# SparkFun_Thing_Plus_RA6M5.net
KiCad netlist of a schematic drawn in EAGLE
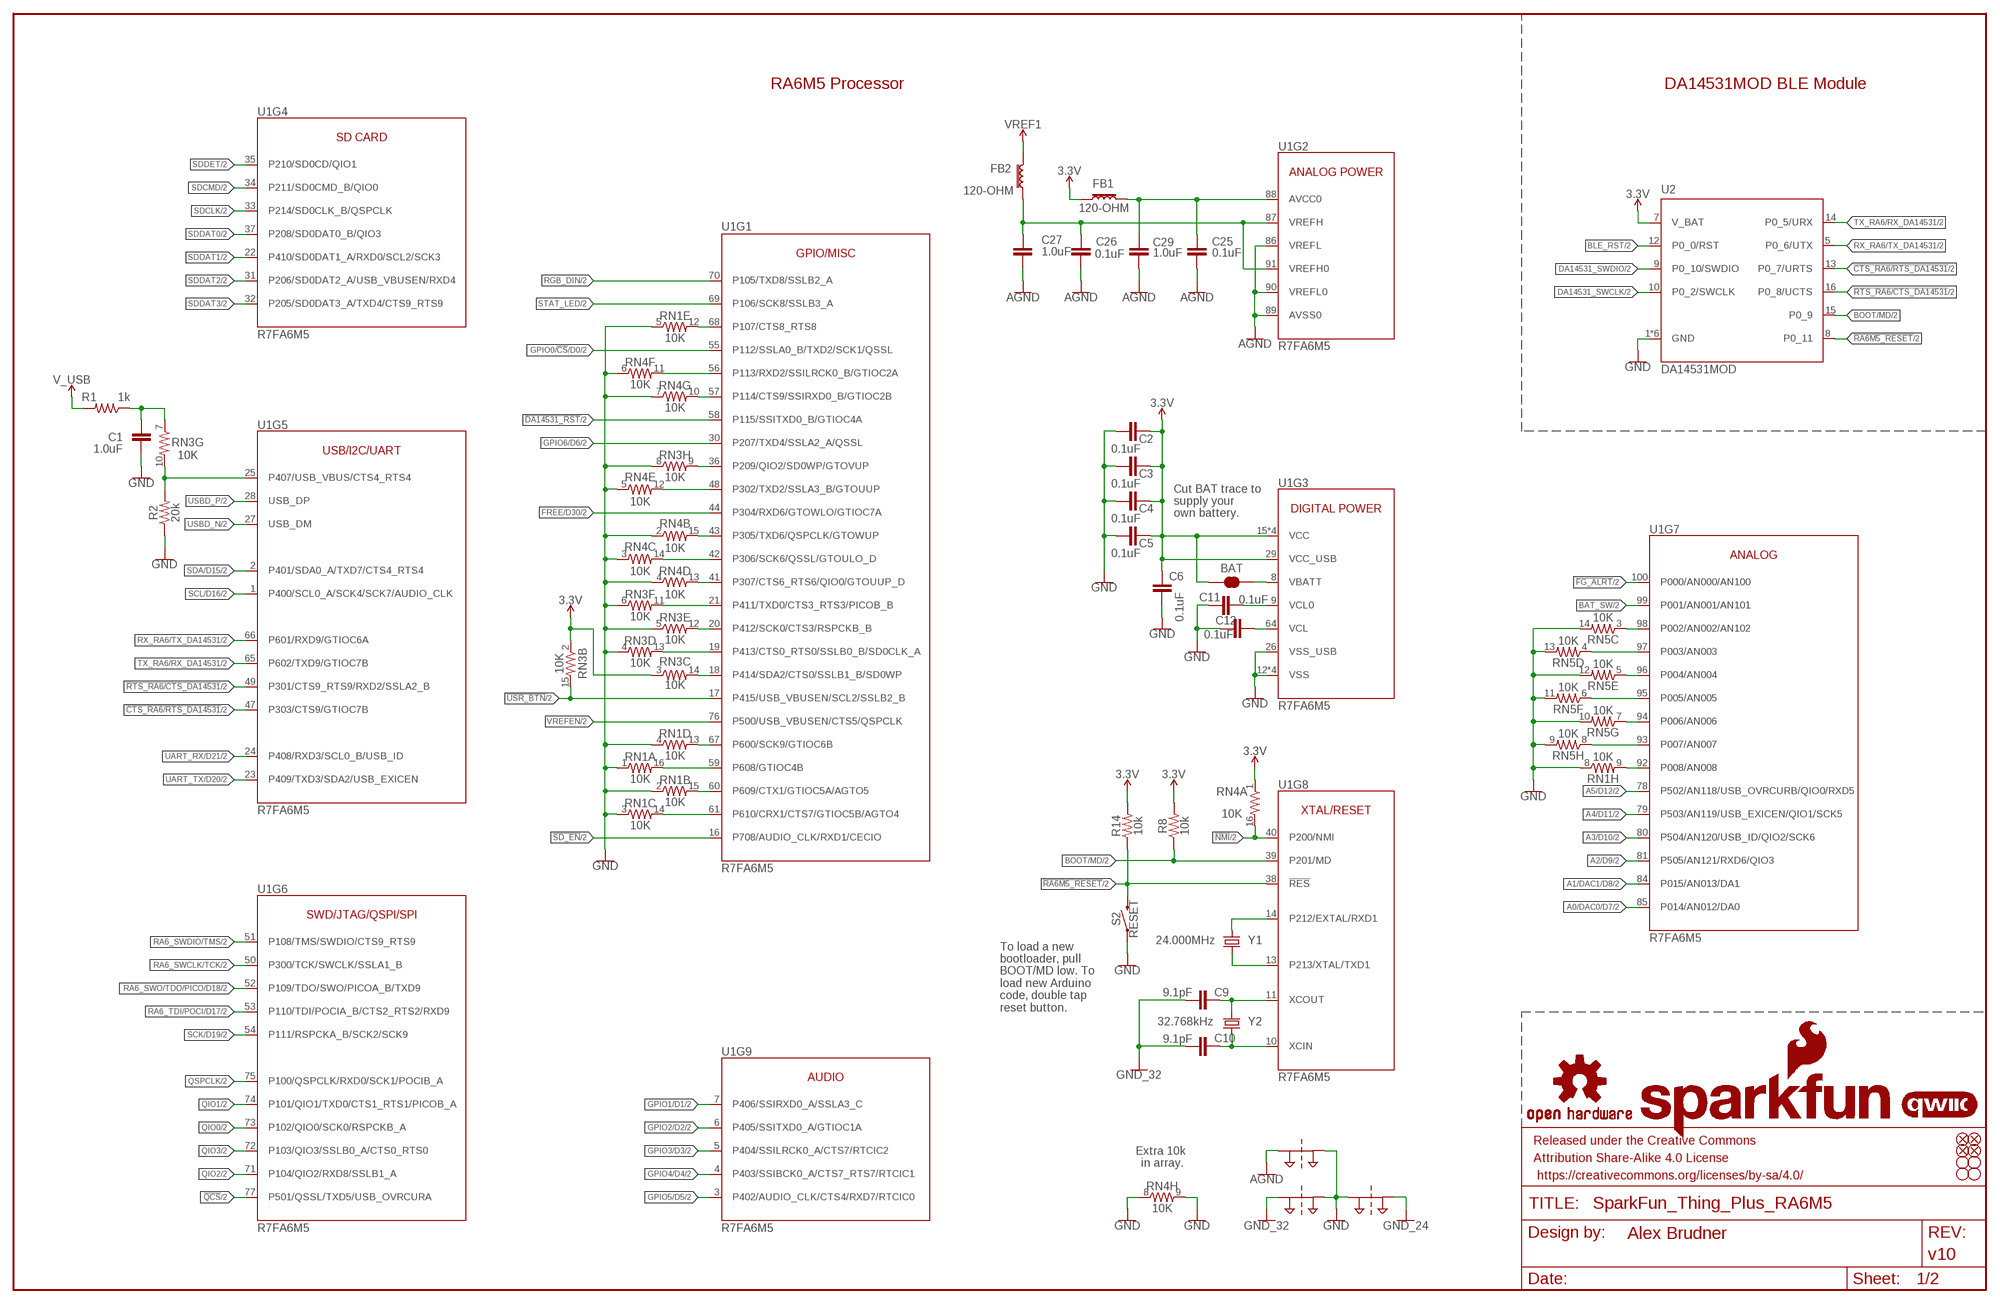
[diagram p0: schematic, sheet 1]
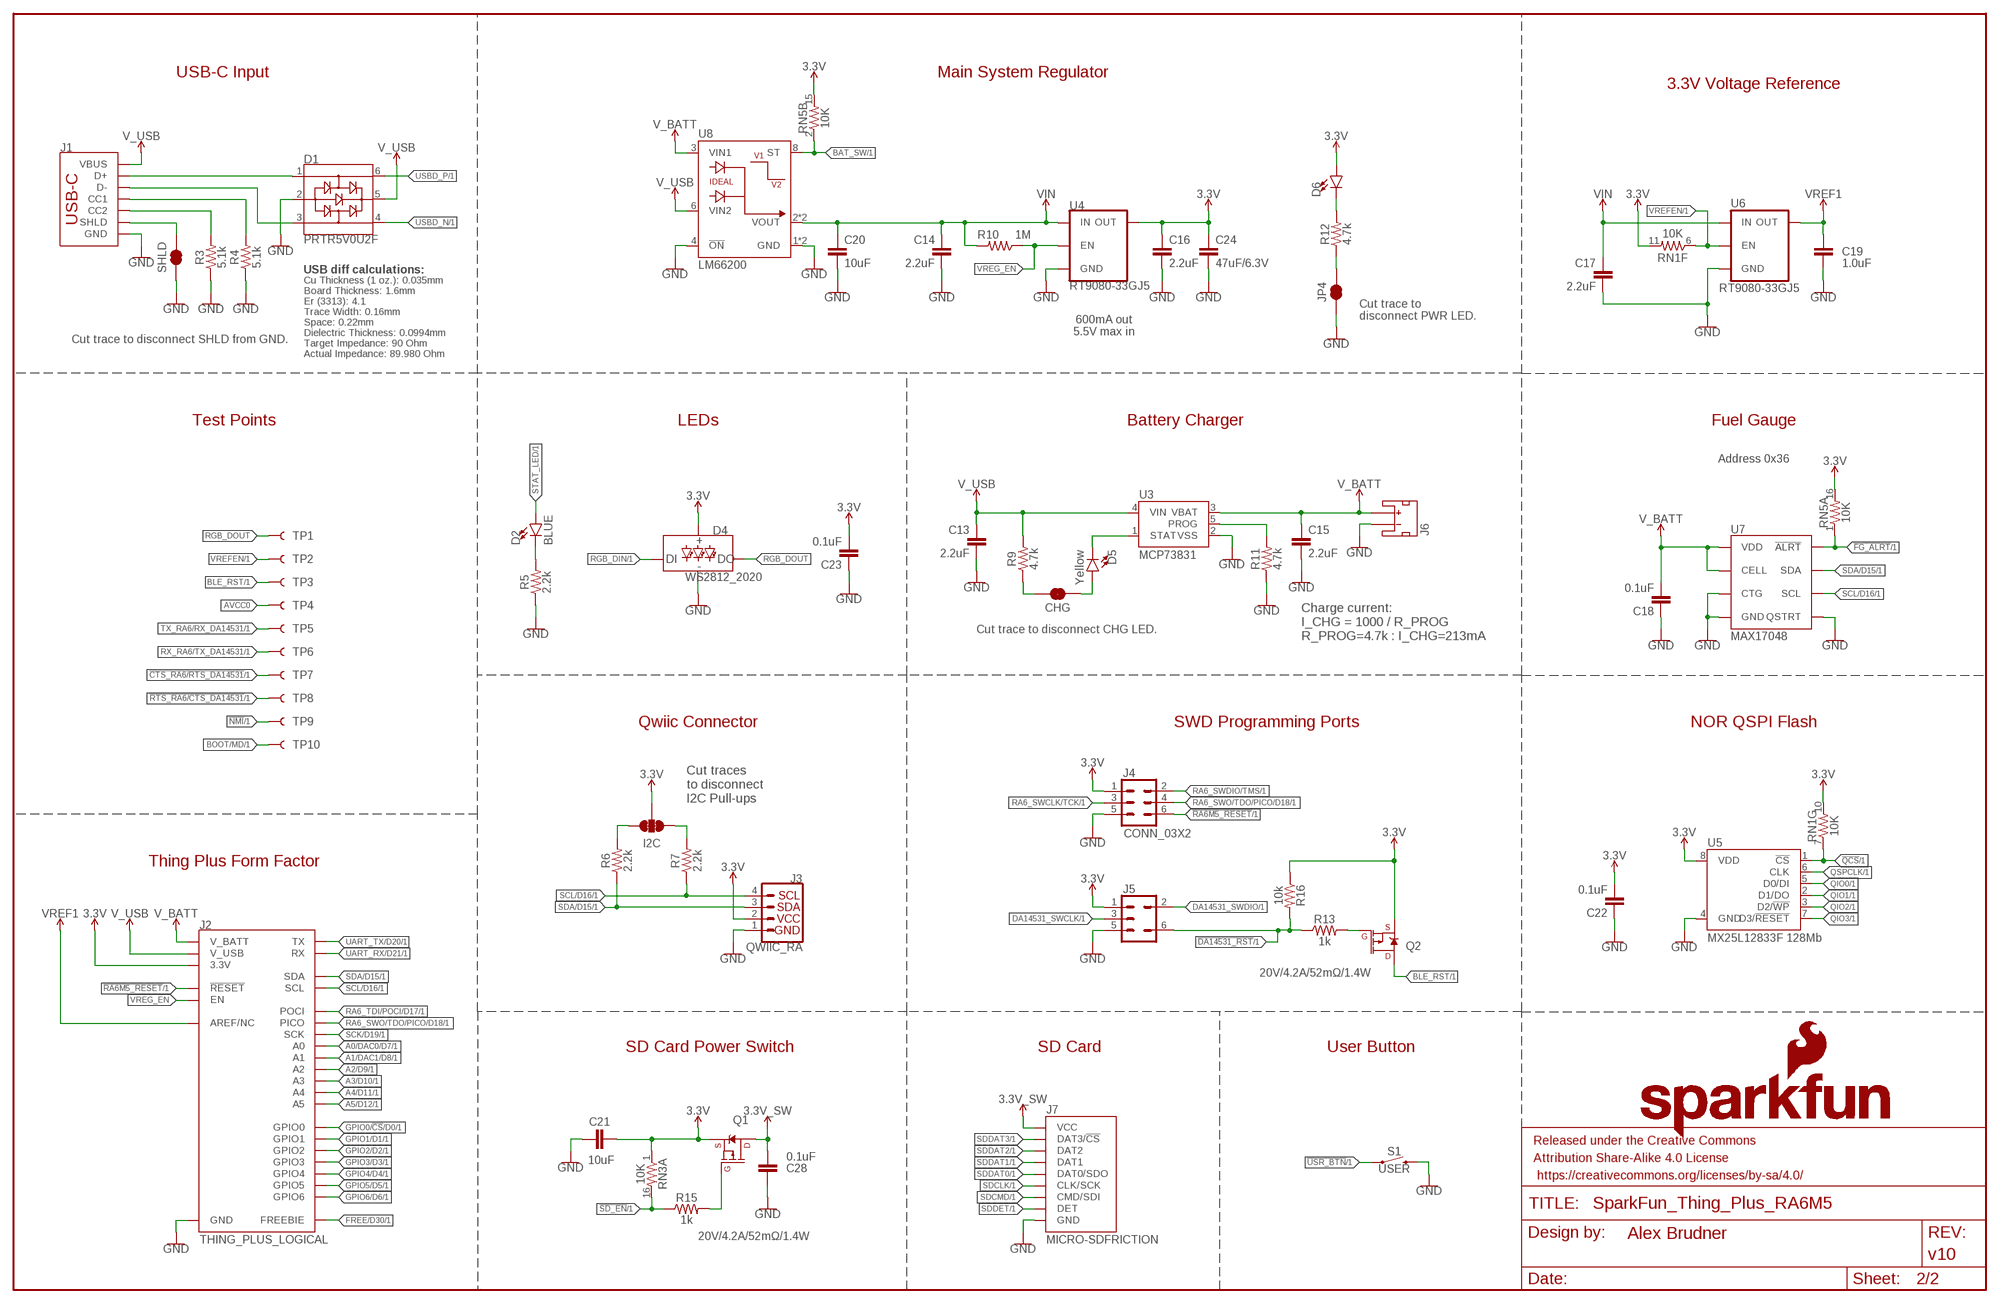
[diagram p1: schematic, sheet 2]

(export (version "E")
  (design (tool "Eeschema 10.0.6"))
  (components
    (comp (ref "BAT")
      (value "JUMPER-SMT_2_NC_TRACE_SILK")
      (footprint "eagle-import:SMT-JUMPER_2_NC_TRACE_SILK")
      (libsource (lib "eagle-import") (part "JUMPER-SMT_2_NC_TRACE_SILK"))
    )
    (comp (ref "C1")
      (value "1.0uF")
      (footprint "eagle-import:0402-TIGHT")
      (libsource (lib "eagle-import") (part "1.0UF-0402T-16V-10%"))
    )
    (comp (ref "C2")
      (value "0.1uF")
      (footprint "eagle-import:0402-TIGHT")
      (libsource (lib "eagle-import") (part "0.1UF-0402T-16V-10%"))
    )
    (comp (ref "C3")
      (value "0.1uF")
      (footprint "eagle-import:0402-TIGHT")
      (libsource (lib "eagle-import") (part "0.1UF-0402T-16V-10%"))
    )
    (comp (ref "C4")
      (value "0.1uF")
      (footprint "eagle-import:0402-TIGHT")
      (libsource (lib "eagle-import") (part "0.1UF-0402T-16V-10%"))
    )
    (comp (ref "C5")
      (value "0.1uF")
      (footprint "eagle-import:0402-TIGHT")
      (libsource (lib "eagle-import") (part "0.1UF-0402T-16V-10%"))
    )
    (comp (ref "C6")
      (value "0.1uF")
      (footprint "eagle-import:0402-TIGHT")
      (libsource (lib "eagle-import") (part "0.1UF-0402T-16V-10%"))
    )
    (comp (ref "C9")
      (value "9.1pF")
      (footprint "eagle-import:0402-TIGHT")
      (fields (field (name "MOUSER_PART") "609-500R07S9R1CV4T"))
      (libsource (lib "eagle-import") (part "9.1PF-0402-TIGHT"))
    )
    (comp (ref "C10")
      (value "9.1pF")
      (footprint "eagle-import:0402-TIGHT")
      (fields (field (name "MOUSER_PART") "609-500R07S9R1CV4T"))
      (libsource (lib "eagle-import") (part "9.1PF-0402-TIGHT"))
    )
    (comp (ref "C11")
      (value "0.1uF")
      (footprint "eagle-import:0402-TIGHT")
      (libsource (lib "eagle-import") (part "0.1UF-0402T-16V-10%"))
    )
    (comp (ref "C12")
      (value "0.1uF")
      (footprint "eagle-import:0402-TIGHT")
      (libsource (lib "eagle-import") (part "0.1UF-0402T-16V-10%"))
    )
    (comp (ref "C25")
      (value "0.1uF")
      (footprint "eagle-import:0402-TIGHT")
      (libsource (lib "eagle-import") (part "0.1UF-0402T-16V-10%"))
    )
    (comp (ref "C26")
      (value "0.1uF")
      (footprint "eagle-import:0402-TIGHT")
      (libsource (lib "eagle-import") (part "0.1UF-0402T-16V-10%"))
    )
    (comp (ref "C27")
      (value "1.0uF")
      (footprint "eagle-import:0402-TIGHT")
      (libsource (lib "eagle-import") (part "1.0UF-0402T-16V-10%"))
    )
    (comp (ref "C29")
      (value "1.0uF")
      (footprint "eagle-import:0402-TIGHT")
      (libsource (lib "eagle-import") (part "1.0UF-0402T-16V-10%"))
    )
    (comp (ref "FB1")
      (value "120-OHM")
      (footprint "eagle-import:0402-TIGHT")
      (libsource (lib "eagle-import") (part "FERRITE_BEAD-120_OHM-0402T"))
    )
    (comp (ref "FB2")
      (value "120-OHM")
      (footprint "eagle-import:0402-TIGHT")
      (libsource (lib "eagle-import") (part "FERRITE_BEAD-120_OHM-0402T"))
    )
    (comp (ref "FD1")
      (value "FIDUCIALUFIDUCIAL")
      (footprint "eagle-import:FIDUCIAL-MICRO")
      (libsource (lib "eagle-import") (part "FIDUCIALUFIDUCIAL"))
    )
    (comp (ref "FD2")
      (value "FIDUCIALUFIDUCIAL")
      (footprint "eagle-import:FIDUCIAL-MICRO")
      (libsource (lib "eagle-import") (part "FIDUCIALUFIDUCIAL"))
    )
    (comp (ref "FD3")
      (value "FIDUCIALUFIDUCIAL")
      (footprint "eagle-import:FIDUCIAL-MICRO")
      (libsource (lib "eagle-import") (part "FIDUCIALUFIDUCIAL"))
    )
    (comp (ref "FD4")
      (value "FIDUCIALUFIDUCIAL")
      (footprint "eagle-import:FIDUCIAL-MICRO")
      (libsource (lib "eagle-import") (part "FIDUCIALUFIDUCIAL"))
    )
    (comp (ref "FRAME1")
      (value "FRAME-LEDGER")
      (footprint "eagle-import:CREATIVE_COMMONS")
      (fields (field (name "DESIGNER") "Alex Brudner") (field (name "REV") "v10"))
      (libsource (lib "eagle-import") (part "FRAME-LEDGER"))
    )
    (comp (ref "H1")
      (value "STAND-OFFTIGHT")
      (footprint "eagle-import:STAND-OFF-TIGHT")
      (libsource (lib "eagle-import") (part "STAND-OFFTIGHT"))
    )
    (comp (ref "H2")
      (value "STAND-OFFTIGHT")
      (footprint "eagle-import:STAND-OFF-TIGHT")
      (libsource (lib "eagle-import") (part "STAND-OFFTIGHT"))
    )
    (comp (ref "H3")
      (value "STAND-OFFTIGHT")
      (footprint "eagle-import:STAND-OFF-TIGHT")
      (libsource (lib "eagle-import") (part "STAND-OFFTIGHT"))
    )
    (comp (ref "H4")
      (value "STAND-OFFTIGHT")
      (footprint "eagle-import:STAND-OFF-TIGHT")
      (libsource (lib "eagle-import") (part "STAND-OFFTIGHT"))
    )
    (comp (ref "LOGO1")
      (value "OSHW-LOGOMINI")
      (footprint "eagle-import:OSHW-LOGO-MINI")
      (libsource (lib "eagle-import") (part "OSHW-LOGOMINI"))
    )
    (comp (ref "LOGO2")
      (value "SFE_LOGO_NAME_FLAME.1_INCH")
      (footprint "eagle-import:SFE_LOGO_NAME_FLAME_.1")
      (libsource (lib "eagle-import") (part "SFE_LOGO_NAME_FLAME.1_INCH"))
    )
    (comp (ref "LOGO3")
      (value "QWIIC_LOGO_4MM")
      (footprint "eagle-import:QWIIC_4MM")
      (libsource (lib "eagle-import") (part "QWIIC_LOGO_4MM"))
    )
    (comp (ref "R1")
      (value "1k")
      (footprint "eagle-import:0402-TIGHT")
      (libsource (lib "eagle-import") (part "1KOHM-0402T-1/16W-1%"))
    )
    (comp (ref "R2")
      (value "20k")
      (footprint "eagle-import:0402-TIGHT")
      (libsource (lib "eagle-import") (part "20KOHM-0402T-1/16W-1%"))
    )
    (comp (ref "R8")
      (value "10k")
      (footprint "eagle-import:0402-TIGHT")
      (libsource (lib "eagle-import") (part "10KOHM-0402T-1/16W-1%"))
    )
    (comp (ref "R14")
      (value "10k")
      (footprint "eagle-import:0402-TIGHT")
      (libsource (lib "eagle-import") (part "10KOHM-0402T-1/16W-1%"))
    )
    (comp (ref "RN1")
      (value "10K")
      (footprint "eagle-import:2506_AR")
      (libsource (lib "eagle-import") (part "10KOHM-ARRAY(8)-2506_ARV-1/16W-5%"))
    )
    (comp (ref "RN3")
      (value "10K")
      (footprint "eagle-import:2506_AR")
      (libsource (lib "eagle-import") (part "10KOHM-ARRAY(8)-2506_ARV-1/16W-5%"))
    )
    (comp (ref "RN4")
      (value "10K")
      (footprint "eagle-import:2506_AR")
      (libsource (lib "eagle-import") (part "10KOHM-ARRAY(8)-2506_ARV-1/16W-5%"))
    )
    (comp (ref "RN5")
      (value "10K")
      (footprint "eagle-import:2506_AR")
      (libsource (lib "eagle-import") (part "10KOHM-ARRAY(8)-2506_ARV-1/16W-5%"))
    )
    (comp (ref "S2")
      (value "RESET")
      (footprint "eagle-import:TACTILE_SWITCH_SMD_4.6X2.8MM")
      (libsource (lib "eagle-import") (part "MOMENTARY-SWITCH-SPST-SMD-4.6X2.8MM"))
    )
    (comp (ref "SUPPLYTIE1")
      (value "2PT_GND_TIESMALL")
      (footprint "eagle-import:2PT_GND_TIE_SMALL")
      (libsource (lib "eagle-import") (part "2PT_GND_TIESMALL"))
    )
    (comp (ref "SUPPLYTIE2")
      (value "2PT_GND_TIESMALL")
      (footprint "eagle-import:2PT_GND_TIE_SMALL")
      (libsource (lib "eagle-import") (part "2PT_GND_TIESMALL"))
    )
    (comp (ref "SUPPLYTIE3")
      (value "2PT_GND_TIESMALL")
      (footprint "eagle-import:2PT_GND_TIE_SMALL")
      (libsource (lib "eagle-import") (part "2PT_GND_TIESMALL"))
    )
    (comp (ref "U1")
      (value "R7FA6M5")
      (footprint "eagle-import:P-LQFP100-14X14-0.50")
      (libsource (lib "eagle-import") (part "R7FA6M5-100LQFP"))
    )
    (comp (ref "U2")
      (value "DA14531MOD")
      (footprint "eagle-import:DA14531MOD")
      (libsource (lib "eagle-import") (part "DA14531MOD"))
    )
    (comp (ref "Y1")
      (value "24.000MHz")
      (footprint "eagle-import:4-SMD,32X25")
      (libsource (lib "eagle-import") (part "CRYSTAL-24.000MHZ-8PF-4-SMD"))
    )
    (comp (ref "Y2")
      (value "32.768kHz")
      (footprint "eagle-import:CRYSTAL-SMD-3.2X1.5MM")
      (libsource (lib "eagle-import") (part "CRYSTAL-32.768KHZSMD-3.2X1.5"))
    )
    (comp (ref "C13")
      (value "2.2uF")
      (footprint "eagle-import:0402-TIGHT")
      (libsource (lib "eagle-import") (part "2.2UF-0402_TIGHT-10V-10%-X5R"))
    )
    (comp (ref "C14")
      (value "2.2uF")
      (footprint "eagle-import:0402-TIGHT")
      (libsource (lib "eagle-import") (part "2.2UF-0402_TIGHT-10V-10%-X5R"))
    )
    (comp (ref "C15")
      (value "2.2uF")
      (footprint "eagle-import:0402-TIGHT")
      (libsource (lib "eagle-import") (part "2.2UF-0402_TIGHT-10V-10%-X5R"))
    )
    (comp (ref "C16")
      (value "2.2uF")
      (footprint "eagle-import:0402-TIGHT")
      (libsource (lib "eagle-import") (part "2.2UF-0402_TIGHT-10V-10%-X5R"))
    )
    (comp (ref "C17")
      (value "2.2uF")
      (footprint "eagle-import:0402-TIGHT")
      (libsource (lib "eagle-import") (part "2.2UF-0402_TIGHT-10V-10%-X5R"))
    )
    (comp (ref "C18")
      (value "0.1uF")
      (footprint "eagle-import:0402-TIGHT")
      (libsource (lib "eagle-import") (part "0.1UF-0402T-16V-10%"))
    )
    (comp (ref "C19")
      (value "1.0uF")
      (footprint "eagle-import:0402-TIGHT")
      (libsource (lib "eagle-import") (part "1.0UF-0402T-16V-10%"))
    )
    (comp (ref "C20")
      (value "10uF")
      (footprint "eagle-import:0805")
      (libsource (lib "eagle-import") (part "10UF-0805-25V-10%"))
    )
    (comp (ref "C21")
      (value "10uF")
      (footprint "eagle-import:0805")
      (libsource (lib "eagle-import") (part "10UF-0805-25V-10%"))
    )
    (comp (ref "C22")
      (value "0.1uF")
      (footprint "eagle-import:0402-TIGHT")
      (libsource (lib "eagle-import") (part "0.1UF-0402T-16V-10%"))
    )
    (comp (ref "C23")
      (value "0.1uF")
      (footprint "eagle-import:0402-TIGHT")
      (libsource (lib "eagle-import") (part "0.1UF-0402T-16V-10%"))
    )
    (comp (ref "C24")
      (value "47uF/6.3V")
      (footprint "eagle-import:0805")
      (libsource (lib "eagle-import") (part "47UF"))
    )
    (comp (ref "C28")
      (value "0.1uF")
      (footprint "eagle-import:0402-TIGHT")
      (libsource (lib "eagle-import") (part "0.1UF-0402T-16V-10%"))
    )
    (comp (ref "CHG")
      (value "JUMPER-SMT_2_NC_TRACE_SILK")
      (footprint "eagle-import:SMT-JUMPER_2_NC_TRACE_SILK")
      (libsource (lib "eagle-import") (part "JUMPER-SMT_2_NC_TRACE_SILK"))
    )
    (comp (ref "D1")
      (value "PRTR5V0U2F")
      (footprint "eagle-import:SOT886")
      (libsource (lib "eagle-import") (part "PRTR5V0U2F"))
    )
    (comp (ref "D2")
      (value "BLUE")
      (footprint "eagle-import:LED-0603")
      (libsource (lib "eagle-import") (part "LED-BLUE0603"))
    )
    (comp (ref "D4")
      (value "WS2812_2020")
      (footprint "eagle-import:WS2812-2020")
      (libsource (lib "eagle-import") (part "WS2812_2020"))
    )
    (comp (ref "D5")
      (value "Yellow")
      (footprint "eagle-import:LED-0603")
      (libsource (lib "eagle-import") (part "LED-YELLOW0603"))
    )
    (comp (ref "D6")
      (value "LED-RED_0603-KB")
      (footprint "eagle-import:LED-0603")
      (libsource (lib "eagle-import") (part "LED-RED_0603-KB"))
    )
    (comp (ref "FRAME2")
      (value "FRAME-LEDGERNO_FOOTPRINT")
      (footprint "eagle-import:DUMMY")
      (fields (field (name "DESIGNER") "Alex Brudner") (field (name "REV") "v10"))
      (libsource (lib "eagle-import") (part "FRAME-LEDGERNO_FOOTPRINT"))
    )
    (comp (ref "I2C")
      (value "JUMPER-SMT_3_2-NC_TRACE_SILK")
      (footprint "eagle-import:SMT-JUMPER_3_2-NC_TRACE_SILK")
      (libsource (lib "eagle-import") (part "JUMPER-SMT_3_2-NC_TRACE_SILK"))
    )
    (comp (ref "J1")
      (value "USB Female Type C Connector")
      (footprint "eagle-import:USB-C-16P-6LAYER-ISOLATED")
      (libsource (lib "eagle-import") (part "USB_C_6-LAYER-ISOLATED"))
    )
    (comp (ref "J2")
      (value "THING_PLUS_LOGICAL")
      (footprint "eagle-import:THING_PLUS")
      (libsource (lib "eagle-import") (part "THING_PLUS_LOGICAL"))
    )
    (comp (ref "J3")
      (value "QWIIC_RA")
      (footprint "eagle-import:JST04_1MM_RA")
      (libsource (lib "eagle-import") (part "QWIIC_CONNECTORJS-1MM"))
    )
    (comp (ref "J4")
      (value "CONN_03X2")
      (footprint "eagle-import:PAD_05_03X2_TP")
      (libsource (lib "eagle-import") (part "CONN_03X2"))
    )
    (comp (ref "J5")
      (value "SWD-5PIN")
      (footprint "eagle-import:PAD_05_03X2_TP_NO4")
      (libsource (lib "eagle-import") (part "SWD-5PIN"))
    )
    (comp (ref "J6")
      (value "JST_2MM_MALE")
      (footprint "eagle-import:JST-2-SMD")
      (libsource (lib "eagle-import") (part "JST_2MM_MALE"))
    )
    (comp (ref "J7")
      (value "MICRO-SDFRICTION")
      (footprint "eagle-import:MICROSD_TINY")
      (libsource (lib "eagle-import") (part "MICRO-SDFRICTION"))
    )
    (comp (ref "JP4")
      (value "JUMPER-SMT_2_NC_TRACE_SILK")
      (footprint "eagle-import:SMT-JUMPER_2_NC_TRACE_SILK")
      (libsource (lib "eagle-import") (part "JUMPER-SMT_2_NC_TRACE_SILK"))
    )
    (comp (ref "LOGO4")
      (value "SFE_LOGO_NAME_FLAMEBLANK")
      (footprint "eagle-import:BLANK")
      (libsource (lib "eagle-import") (part "SFE_LOGO_NAME_FLAMEBLANK"))
    )
    (comp (ref "Q1")
      (value "20V/4.2A/52mΩ/1.4W")
      (footprint "eagle-import:SOT23-3")
      (libsource (lib "eagle-import") (part "MOSFET_PCH-DMG2305UX-7"))
    )
    (comp (ref "Q2")
      (value "20V/4.2A/52mΩ/1.4W")
      (footprint "eagle-import:SOT23-3")
      (libsource (lib "eagle-import") (part "MOSFET_PCH-DMG2305UX-7"))
    )
    (comp (ref "R3")
      (value "5.1k")
      (footprint "eagle-import:0402-TIGHT")
      (libsource (lib "eagle-import") (part "5.1KOHM-0402T-1/16W-1%"))
    )
    (comp (ref "R4")
      (value "5.1k")
      (footprint "eagle-import:0402-TIGHT")
      (libsource (lib "eagle-import") (part "5.1KOHM-0402T-1/16W-1%"))
    )
    (comp (ref "R5")
      (value "2.2k")
      (footprint "eagle-import:0402-TIGHT")
      (libsource (lib "eagle-import") (part "2.2KOHM-0402T-1/16W-1%"))
    )
    (comp (ref "R6")
      (value "2.2k")
      (footprint "eagle-import:0402-TIGHT")
      (libsource (lib "eagle-import") (part "2.2KOHM-0402T-1/16W-1%"))
    )
    (comp (ref "R7")
      (value "2.2k")
      (footprint "eagle-import:0402-TIGHT")
      (libsource (lib "eagle-import") (part "2.2KOHM-0402T-1/16W-1%"))
    )
    (comp (ref "R9")
      (value "4.7k")
      (footprint "eagle-import:0402-TIGHT")
      (libsource (lib "eagle-import") (part "4.7KOHM-0402T-1/16W-1%"))
    )
    (comp (ref "R10")
      (value "1M")
      (footprint "eagle-import:0402-TIGHT")
      (libsource (lib "eagle-import") (part "1MOHM-0402T-1/16W-5%"))
    )
    (comp (ref "R11")
      (value "4.7k")
      (footprint "eagle-import:0402-TIGHT")
      (libsource (lib "eagle-import") (part "4.7KOHM-0402T-1/16W-1%"))
    )
    (comp (ref "R12")
      (value "4.7k")
      (footprint "eagle-import:0402-TIGHT")
      (libsource (lib "eagle-import") (part "4.7KOHM-0402T-1/16W-1%"))
    )
    (comp (ref "R13")
      (value "1k")
      (footprint "eagle-import:0402-TIGHT")
      (libsource (lib "eagle-import") (part "1KOHM-0402T-1/16W-1%"))
    )
    (comp (ref "R15")
      (value "1k")
      (footprint "eagle-import:0402-TIGHT")
      (libsource (lib "eagle-import") (part "1KOHM-0402T-1/16W-1%"))
    )
    (comp (ref "R16")
      (value "10k")
      (footprint "eagle-import:0402-TIGHT")
      (libsource (lib "eagle-import") (part "10KOHM-0402T-1/16W-1%"))
    )
    (comp (ref "S1")
      (value "USER")
      (footprint "eagle-import:TACTILE_SWITCH_SMD_4.6X2.8MM")
      (libsource (lib "eagle-import") (part "MOMENTARY-SWITCH-SPST-SMD-4.6X2.8MM"))
    )
    (comp (ref "SHLD")
      (value "JUMPER-SMT_2_NC_TRACE_SILK")
      (footprint "eagle-import:SMT-JUMPER_2_NC_TRACE_SILK")
      (libsource (lib "eagle-import") (part "JUMPER-SMT_2_NC_TRACE_SILK"))
    )
    (comp (ref "TP1")
      (value "TEST-POINT3X5")
      (footprint "eagle-import:PAD.03X.05")
      (libsource (lib "eagle-import") (part "TEST-POINT3X5"))
    )
    (comp (ref "TP2")
      (value "TEST-POINT3X4")
      (footprint "eagle-import:PAD.03X.04")
      (libsource (lib "eagle-import") (part "TEST-POINT3X4"))
    )
    (comp (ref "TP3")
      (value "TEST-POINT3X5")
      (footprint "eagle-import:PAD.03X.05")
      (libsource (lib "eagle-import") (part "TEST-POINT3X5"))
    )
    (comp (ref "TP4")
      (value "TEST-POINT3")
      (footprint "eagle-import:PAD.03X.03")
      (libsource (lib "eagle-import") (part "TEST-POINT3"))
    )
    (comp (ref "TP5")
      (value "TEST-POINT3X5")
      (footprint "eagle-import:PAD.03X.05")
      (libsource (lib "eagle-import") (part "TEST-POINT3X5"))
    )
    (comp (ref "TP6")
      (value "TEST-POINT3X5")
      (footprint "eagle-import:PAD.03X.05")
      (libsource (lib "eagle-import") (part "TEST-POINT3X5"))
    )
    (comp (ref "TP7")
      (value "TEST-POINT3X5")
      (footprint "eagle-import:PAD.03X.05")
      (libsource (lib "eagle-import") (part "TEST-POINT3X5"))
    )
    (comp (ref "TP8")
      (value "TEST-POINT3X5")
      (footprint "eagle-import:PAD.03X.05")
      (libsource (lib "eagle-import") (part "TEST-POINT3X5"))
    )
    (comp (ref "TP9")
      (value "TEST-POINT3")
      (footprint "eagle-import:PAD.03X.03")
      (libsource (lib "eagle-import") (part "TEST-POINT3"))
    )
    (comp (ref "TP10")
      (value "TEST-POINT3X5")
      (footprint "eagle-import:PAD.03X.05")
      (libsource (lib "eagle-import") (part "TEST-POINT3X5"))
    )
    (comp (ref "U3")
      (value "MCP73831")
      (footprint "eagle-import:SOT23-5")
      (libsource (lib "eagle-import") (part "MCP73831"))
    )
    (comp (ref "U4")
      (value "RT9080-33GJ5")
      (footprint "eagle-import:SOT23-5")
      (libsource (lib "eagle-import") (part "V_REG_RT9080"))
    )
    (comp (ref "U5")
      (value "MX25L12833F 128Mb")
      (footprint "eagle-import:WSON-8-6X5")
      (libsource (lib "eagle-import") (part "MX25L12833F_128MBIT_QSPI"))
    )
    (comp (ref "U6")
      (value "RT9080-33GJ5")
      (footprint "eagle-import:SOT23-5")
      (libsource (lib "eagle-import") (part "V_REG_RT9080"))
    )
    (comp (ref "U7")
      (value "MAX17048")
      (footprint "eagle-import:DFN-8")
      (libsource (lib "eagle-import") (part "MAX17048DFN8"))
    )
    (comp (ref "U8")
      (value "LM66200")
      (footprint "eagle-import:SOT8")
      (libsource (lib "eagle-import") (part "IDEAL_DIODE_DUAL_LM66200"))
    )
  )
  (nets
    (net (code "1") (name "3.3V") (class "Default")
      (node (ref "BAT") (pin "1") (pinfunction "1_1") (pintype "passive"))
      (node (ref "C16") (pin "1") (pinfunction "1_1") (pintype "passive"))
      (node (ref "C2") (pin "1") (pinfunction "1_1") (pintype "passive"))
      (node (ref "C21") (pin "1") (pinfunction "1_1") (pintype "passive"))
      (node (ref "C22") (pin "2") (pinfunction "2_2") (pintype "passive"))
      (node (ref "C23") (pin "2") (pinfunction "2_2") (pintype "passive"))
      (node (ref "C24") (pin "1") (pinfunction "1_1") (pintype "passive"))
      (node (ref "C3") (pin "1") (pinfunction "1_1") (pintype "passive"))
      (node (ref "C4") (pin "1") (pinfunction "1_1") (pintype "passive"))
      (node (ref "C5") (pin "1") (pinfunction "1_1") (pintype "passive"))
      (node (ref "C6") (pin "1") (pinfunction "1_1") (pintype "passive"))
      (node (ref "D4") (pin "VCC") (pinfunction "VCC_VCC") (pintype "bidirectional"))
      (node (ref "D6") (pin "A") (pinfunction "A_A") (pintype "passive"))
      (node (ref "FB1") (pin "1") (pinfunction "1_1") (pintype "passive"))
      (node (ref "I2C") (pin "2") (pinfunction "2_2") (pintype "passive"))
      (node (ref "J2") (pin "27") (pinfunction "3.3V_27") (pintype "bidirectional"))
      (node (ref "J3") (pin "2") (pinfunction "2_2") (pintype "power_in"))
      (node (ref "J4") (pin "1") (pinfunction "1_1") (pintype "bidirectional"))
      (node (ref "J5") (pin "1") (pinfunction "1_1") (pintype "bidirectional"))
      (node (ref "Q1") (pin "2") (pinfunction "S_2") (pintype "bidirectional"))
      (node (ref "Q2") (pin "2") (pinfunction "S_2") (pintype "bidirectional"))
      (node (ref "R14") (pin "2") (pinfunction "2_2") (pintype "passive"))
      (node (ref "R16") (pin "1") (pinfunction "1_1") (pintype "passive"))
      (node (ref "R8") (pin "2") (pinfunction "2_2") (pintype "passive"))
      (node (ref "RN1") (pin "10") (pinfunction "2_10") (pintype "passive"))
      (node (ref "RN1") (pin "11") (pinfunction "2_11") (pintype "passive"))
      (node (ref "RN3") (pin "1") (pinfunction "1_1") (pintype "passive"))
      (node (ref "RN3") (pin "2") (pinfunction "1_2") (pintype "passive"))
      (node (ref "RN3") (pin "3") (pinfunction "1_3") (pintype "passive"))
      (node (ref "RN4") (pin "1") (pinfunction "1_1") (pintype "passive"))
      (node (ref "RN5") (pin "15") (pinfunction "2_15") (pintype "passive"))
      (node (ref "RN5") (pin "16") (pinfunction "2_16") (pintype "passive"))
      (node (ref "U1") (pin "15") (pinfunction "VCC_15") (pintype "bidirectional"))
      (node (ref "U1") (pin "29") (pinfunction "VCC_USB_29") (pintype "bidirectional"))
      (node (ref "U1") (pin "46") (pinfunction "VCC_46") (pintype "bidirectional"))
      (node (ref "U1") (pin "62") (pinfunction "VCC_62") (pintype "bidirectional"))
      (node (ref "U1") (pin "82") (pinfunction "VCC_82") (pintype "bidirectional"))
      (node (ref "U2") (pin "7") (pinfunction "V_BAT_7") (pintype "bidirectional"))
      (node (ref "U4") (pin "5") (pinfunction "OUT_5") (pintype "passive"))
      (node (ref "U5") (pin "8") (pinfunction "VDD_8") (pintype "bidirectional"))
    )
    (net (code "2") (name "3.3V_SW") (class "Default")
      (node (ref "C28") (pin "2") (pinfunction "2_2") (pintype "passive"))
      (node (ref "J7") (pin "4") (pinfunction "VCC_4") (pintype "bidirectional"))
      (node (ref "Q1") (pin "3") (pinfunction "D_3") (pintype "bidirectional"))
    )
    (net (code "3") (name "A0{slash}DAC0{slash}D7") (class "Default")
      (node (ref "J2") (pin "24") (pinfunction "A0_24") (pintype "bidirectional"))
      (node (ref "U1") (pin "85") (pinfunction "P014/AN012/DA0_85") (pintype "bidirectional"))
    )
    (net (code "4") (name "A1{slash}DAC1{slash}D8") (class "Default")
      (node (ref "J2") (pin "23") (pinfunction "A1_23") (pintype "bidirectional"))
      (node (ref "U1") (pin "84") (pinfunction "P015/AN013/DA1_84") (pintype "bidirectional"))
    )
    (net (code "5") (name "A2{slash}D9") (class "Default")
      (node (ref "J2") (pin "22") (pinfunction "A2_22") (pintype "bidirectional"))
      (node (ref "U1") (pin "81") (pinfunction "P505/AN121/RXD6/QIO3_81") (pintype "bidirectional"))
    )
    (net (code "6") (name "A3{slash}D10") (class "Default")
      (node (ref "J2") (pin "21") (pinfunction "A3_21") (pintype "bidirectional"))
      (node (ref "U1") (pin "80") (pinfunction "P504/AN120/USB_ID/QIO2/SCK6_80") (pintype "bidirectional"))
    )
    (net (code "7") (name "A4{slash}D11") (class "Default")
      (node (ref "J2") (pin "20") (pinfunction "A4_20") (pintype "bidirectional"))
      (node (ref "U1") (pin "79") (pinfunction "P503/AN119/USB_EXICEN/QIO1/SCK5_79") (pintype "bidirectional"))
    )
    (net (code "8") (name "A5{slash}D12") (class "Default")
      (node (ref "J2") (pin "19") (pinfunction "A5_19") (pintype "bidirectional"))
      (node (ref "U1") (pin "78") (pinfunction "P502/AN118/USB_OVRCURB/QIO0/RXD5_78") (pintype "bidirectional"))
    )
    (net (code "9") (name "AGND") (class "Default")
      (node (ref "C25") (pin "2") (pinfunction "2_2") (pintype "passive"))
      (node (ref "C26") (pin "2") (pinfunction "2_2") (pintype "passive"))
      (node (ref "C27") (pin "2") (pinfunction "2_2") (pintype "passive"))
      (node (ref "C29") (pin "2") (pinfunction "2_2") (pintype "passive"))
      (node (ref "SUPPLYTIE1") (pin "P$1") (pinfunction "P$1_P$1") (pintype "bidirectional"))
      (node (ref "U1") (pin "86") (pinfunction "VREFL_86") (pintype "bidirectional"))
      (node (ref "U1") (pin "89") (pinfunction "AVSS0_89") (pintype "bidirectional"))
      (node (ref "U1") (pin "90") (pinfunction "VREFL0_90") (pintype "bidirectional"))
    )
    (net (code "10") (name "AVCC0") (class "Default")
      (node (ref "C25") (pin "1") (pinfunction "1_1") (pintype "passive"))
      (node (ref "C29") (pin "1") (pinfunction "1_1") (pintype "passive"))
      (node (ref "FB1") (pin "2") (pinfunction "2_2") (pintype "passive"))
      (node (ref "TP4") (pin "1") (pinfunction "1_1") (pintype "bidirectional"))
      (node (ref "U1") (pin "88") (pinfunction "AVCC0_88") (pintype "bidirectional"))
    )
    (net (code "11") (name "BAT_SW") (class "Default")
      (node (ref "RN5") (pin "2") (pinfunction "1_2") (pintype "passive"))
      (node (ref "U1") (pin "99") (pinfunction "P001/AN001/AN101_99") (pintype "bidirectional"))
      (node (ref "U8") (pin "8") (pinfunction "ST_8") (pintype "bidirectional"))
    )
    (net (code "12") (name "BLE_RST") (class "Default")
      (node (ref "Q2") (pin "3") (pinfunction "D_3") (pintype "bidirectional"))
      (node (ref "TP3") (pin "1") (pinfunction "1_1") (pintype "bidirectional"))
      (node (ref "U2") (pin "12") (pinfunction "P0_0/RST_12") (pintype "bidirectional"))
    )
    (net (code "13") (name "BOOT{slash}MD") (class "Default")
      (node (ref "R8") (pin "1") (pinfunction "1_1") (pintype "passive"))
      (node (ref "TP10") (pin "1") (pinfunction "1_1") (pintype "bidirectional"))
      (node (ref "U1") (pin "39") (pinfunction "P201/MD_39") (pintype "bidirectional"))
      (node (ref "U2") (pin "15") (pinfunction "P0_9_15") (pintype "bidirectional"))
    )
    (net (code "14") (name "DA14531_SWCLK") (class "Default")
      (node (ref "J5") (pin "3") (pinfunction "3_3") (pintype "bidirectional"))
      (node (ref "U2") (pin "10") (pinfunction "P0_2/SWCLK_10") (pintype "bidirectional"))
    )
    (net (code "15") (name "DA14531_SWDIO") (class "Default")
      (node (ref "J5") (pin "2") (pinfunction "2_2") (pintype "bidirectional"))
      (node (ref "U2") (pin "9") (pinfunction "P0_10/SWDIO_9") (pintype "bidirectional"))
    )
    (net (code "16") (name "FREE{slash}D30") (class "Default")
      (node (ref "J2") (pin "13") (pinfunction "FREEBIE_13") (pintype "bidirectional"))
      (node (ref "U1") (pin "44") (pinfunction "P304/RXD6/GTOWLO/GTIOC7A_44") (pintype "bidirectional"))
    )
    (net (code "17") (name "GND") (class "Default")
      (node (ref "C1") (pin "1") (pinfunction "1_1") (pintype "passive"))
      (node (ref "C11") (pin "2") (pinfunction "2_2") (pintype "passive"))
      (node (ref "C12") (pin "2") (pinfunction "2_2") (pintype "passive"))
      (node (ref "C13") (pin "2") (pinfunction "2_2") (pintype "passive"))
      (node (ref "C14") (pin "2") (pinfunction "2_2") (pintype "passive"))
      (node (ref "C15") (pin "2") (pinfunction "2_2") (pintype "passive"))
      (node (ref "C16") (pin "2") (pinfunction "2_2") (pintype "passive"))
      (node (ref "C17") (pin "2") (pinfunction "2_2") (pintype "passive"))
      (node (ref "C18") (pin "1") (pinfunction "1_1") (pintype "passive"))
      (node (ref "C19") (pin "2") (pinfunction "2_2") (pintype "passive"))
      (node (ref "C2") (pin "2") (pinfunction "2_2") (pintype "passive"))
      (node (ref "C20") (pin "2") (pinfunction "2_2") (pintype "passive"))
      (node (ref "C21") (pin "2") (pinfunction "2_2") (pintype "passive"))
      (node (ref "C22") (pin "1") (pinfunction "1_1") (pintype "passive"))
      (node (ref "C23") (pin "1") (pinfunction "1_1") (pintype "passive"))
      (node (ref "C24") (pin "2") (pinfunction "2_2") (pintype "passive"))
      (node (ref "C28") (pin "1") (pinfunction "1_1") (pintype "passive"))
      (node (ref "C3") (pin "2") (pinfunction "2_2") (pintype "passive"))
      (node (ref "C4") (pin "2") (pinfunction "2_2") (pintype "passive"))
      (node (ref "C5") (pin "2") (pinfunction "2_2") (pintype "passive"))
      (node (ref "C6") (pin "2") (pinfunction "2_2") (pintype "passive"))
      (node (ref "D1") (pin "2") (pinfunction "2_2") (pintype "power_in"))
      (node (ref "D4") (pin "GND") (pinfunction "GND_GND") (pintype "bidirectional"))
      (node (ref "J1") (pin "GND") (pinfunction "GND_GND") (pintype "bidirectional"))
      (node (ref "J1") (pin "GND2") (pinfunction "GND_GND2") (pintype "bidirectional"))
      (node (ref "J2") (pin "25") (pinfunction "GND_25") (pintype "bidirectional"))
      (node (ref "J3") (pin "1") (pinfunction "1_1") (pintype "power_in"))
      (node (ref "J4") (pin "5") (pinfunction "5_5") (pintype "bidirectional"))
      (node (ref "J5") (pin "5") (pinfunction "5_5") (pintype "bidirectional"))
      (node (ref "J6") (pin "1") (pinfunction "-_1") (pintype "bidirectional"))
      (node (ref "J7") (pin "6") (pinfunction "GND_6") (pintype "bidirectional"))
      (node (ref "J7") (pin "GND1") (pinfunction "GND_GND1") (pintype "bidirectional"))
      (node (ref "J7") (pin "GND2") (pinfunction "GND_GND2") (pintype "bidirectional"))
      (node (ref "J7") (pin "GND3") (pinfunction "GND_GND3") (pintype "bidirectional"))
      (node (ref "J7") (pin "GND4") (pinfunction "GND_GND4") (pintype "bidirectional"))
      (node (ref "J7") (pin "GND5") (pinfunction "GND_GND5") (pintype "bidirectional"))
      (node (ref "J7") (pin "GND6") (pinfunction "GND_GND6") (pintype "bidirectional"))
      (node (ref "JP4") (pin "1") (pinfunction "1_1") (pintype "passive"))
      (node (ref "R11") (pin "1") (pinfunction "1_1") (pintype "passive"))
      (node (ref "R2") (pin "1") (pinfunction "1_1") (pintype "passive"))
      (node (ref "R3") (pin "1") (pinfunction "1_1") (pintype "passive"))
      (node (ref "R4") (pin "1") (pinfunction "1_1") (pintype "passive"))
      (node (ref "R5") (pin "1") (pinfunction "1_1") (pintype "passive"))
      (node (ref "RN1") (pin "1") (pinfunction "1_1") (pintype "passive"))
      (node (ref "RN1") (pin "2") (pinfunction "1_2") (pintype "passive"))
      (node (ref "RN1") (pin "3") (pinfunction "1_3") (pintype "passive"))
      (node (ref "RN1") (pin "4") (pinfunction "1_4") (pintype "passive"))
      (node (ref "RN1") (pin "5") (pinfunction "1_5") (pintype "passive"))
      (node (ref "RN1") (pin "8") (pinfunction "1_8") (pintype "passive"))
      (node (ref "RN3") (pin "4") (pinfunction "1_4") (pintype "passive"))
      (node (ref "RN3") (pin "5") (pinfunction "1_5") (pintype "passive"))
      (node (ref "RN3") (pin "6") (pinfunction "1_6") (pintype "passive"))
      (node (ref "RN3") (pin "8") (pinfunction "1_8") (pintype "passive"))
      (node (ref "RN4") (pin "2") (pinfunction "1_2") (pintype "passive"))
      (node (ref "RN4") (pin "3") (pinfunction "1_3") (pintype "passive"))
      (node (ref "RN4") (pin "4") (pinfunction "1_4") (pintype "passive"))
      (node (ref "RN4") (pin "5") (pinfunction "1_5") (pintype "passive"))
      (node (ref "RN4") (pin "6") (pinfunction "1_6") (pintype "passive"))
      (node (ref "RN4") (pin "7") (pinfunction "1_7") (pintype "passive"))
      (node (ref "RN4") (pin "8") (pinfunction "1_8") (pintype "passive"))
      (node (ref "RN4") (pin "9") (pinfunction "2_9") (pintype "passive"))
      (node (ref "RN5") (pin "10") (pinfunction "2_10") (pintype "passive"))
      (node (ref "RN5") (pin "11") (pinfunction "2_11") (pintype "passive"))
      (node (ref "RN5") (pin "12") (pinfunction "2_12") (pintype "passive"))
      (node (ref "RN5") (pin "13") (pinfunction "2_13") (pintype "passive"))
      (node (ref "RN5") (pin "14") (pinfunction "2_14") (pintype "passive"))
      (node (ref "RN5") (pin "9") (pinfunction "2_9") (pintype "passive"))
      (node (ref "S1") (pin "3") (pinfunction "2_3") (pintype "passive"))
      (node (ref "S1") (pin "4") (pinfunction "2_4") (pintype "passive"))
      (node (ref "S2") (pin "1") (pinfunction "1_1") (pintype "passive"))
      (node (ref "S2") (pin "2") (pinfunction "1_2") (pintype "passive"))
      (node (ref "SHLD") (pin "1") (pinfunction "1_1") (pintype "passive"))
      (node (ref "SUPPLYTIE1") (pin "P$2") (pinfunction "P$2_P$2") (pintype "bidirectional"))
      (node (ref "SUPPLYTIE2") (pin "P$2") (pinfunction "P$2_P$2") (pintype "bidirectional"))
      (node (ref "SUPPLYTIE3") (pin "P$1") (pinfunction "P$1_P$1") (pintype "bidirectional"))
      (node (ref "U1") (pin "12") (pinfunction "VSS_12") (pintype "bidirectional"))
      (node (ref "U1") (pin "26") (pinfunction "VSS_USB_26") (pintype "bidirectional"))
      (node (ref "U1") (pin "45") (pinfunction "VSS_45") (pintype "bidirectional"))
      (node (ref "U1") (pin "63") (pinfunction "VSS_63") (pintype "bidirectional"))
      (node (ref "U1") (pin "83") (pinfunction "VSS_83") (pintype "bidirectional"))
      (node (ref "U2") (pin "1") (pinfunction "GND_1") (pintype "bidirectional"))
      (node (ref "U2") (pin "11") (pinfunction "GND_11") (pintype "bidirectional"))
      (node (ref "U2") (pin "2") (pinfunction "GND_2") (pintype "bidirectional"))
      (node (ref "U2") (pin "3") (pinfunction "GND_3") (pintype "bidirectional"))
      (node (ref "U2") (pin "4") (pinfunction "GND_4") (pintype "bidirectional"))
      (node (ref "U2") (pin "6") (pinfunction "GND_6") (pintype "bidirectional"))
      (node (ref "U3") (pin "2") (pinfunction "VSS_2") (pintype "power_in"))
      (node (ref "U4") (pin "2") (pinfunction "GND_2") (pintype "input"))
      (node (ref "U5") (pin "4") (pinfunction "GND_4") (pintype "bidirectional"))
      (node (ref "U6") (pin "2") (pinfunction "GND_2") (pintype "input"))
      (node (ref "U7") (pin "1") (pinfunction "CTG_1") (pintype "input"))
      (node (ref "U7") (pin "4") (pinfunction "GND_4") (pintype "bidirectional"))
      (node (ref "U7") (pin "6") (pinfunction "QSTRT_6") (pintype "bidirectional"))
      (node (ref "U7") (pin "9") (pinfunction "GND_9") (pintype "bidirectional"))
      (node (ref "U8") (pin "1") (pinfunction "GND_1") (pintype "bidirectional"))
      (node (ref "U8") (pin "4") (pinfunction "~{ON}_4") (pintype "bidirectional"))
      (node (ref "U8") (pin "5") (pinfunction "GND_5") (pintype "bidirectional"))
    )
    (net (code "18") (name "GND_24") (class "Default")
      (node (ref "SUPPLYTIE3") (pin "P$2") (pinfunction "P$2_P$2") (pintype "bidirectional"))
    )
    (net (code "19") (name "GND_32") (class "Default")
      (node (ref "C10") (pin "1") (pinfunction "1_1") (pintype "passive"))
      (node (ref "C9") (pin "1") (pinfunction "1_1") (pintype "passive"))
      (node (ref "SUPPLYTIE2") (pin "P$1") (pinfunction "P$1_P$1") (pintype "bidirectional"))
    )
    (net (code "20") (name "GPIO0{slash}~{CS}{slash}D0") (class "Default")
      (node (ref "J2") (pin "9") (pinfunction "GPIO0_9") (pintype "bidirectional"))
      (node (ref "U1") (pin "55") (pinfunction "P112/SSLA0_B/TXD2/SCK1/QSSL_55") (pintype "bidirectional"))
    )
    (net (code "21") (name "GPIO1{slash}D1") (class "Default")
      (node (ref "J2") (pin "8") (pinfunction "GPIO1_8") (pintype "bidirectional"))
      (node (ref "U1") (pin "7") (pinfunction "P406/SSIRXD0_A/SSLA3_C_7") (pintype "bidirectional"))
    )
    (net (code "22") (name "GPIO2{slash}D2") (class "Default")
      (node (ref "J2") (pin "7") (pinfunction "GPIO2_7") (pintype "bidirectional"))
      (node (ref "U1") (pin "6") (pinfunction "P405/SSITXD0_A/GTIOC1A_6") (pintype "bidirectional"))
    )
    (net (code "23") (name "GPIO3{slash}D3") (class "Default")
      (node (ref "J2") (pin "6") (pinfunction "GPIO3_6") (pintype "bidirectional"))
      (node (ref "U1") (pin "5") (pinfunction "P404/SSILRCK0_A/CTS7/RTCIC2_5") (pintype "bidirectional"))
    )
    (net (code "24") (name "GPIO4{slash}D4") (class "Default")
      (node (ref "J2") (pin "5") (pinfunction "GPIO4_5") (pintype "bidirectional"))
      (node (ref "U1") (pin "4") (pinfunction "P403/SSIBCK0_A/CTS7_RTS7/RTCIC1_4") (pintype "bidirectional"))
    )
    (net (code "25") (name "GPIO5{slash}D5") (class "Default")
      (node (ref "J2") (pin "4") (pinfunction "GPIO5_4") (pintype "bidirectional"))
      (node (ref "U1") (pin "3") (pinfunction "P402/AUDIO_CLK/CTS4/RXD7/RTCIC0_3") (pintype "bidirectional"))
    )
    (net (code "26") (name "GPIO6{slash}D6") (class "Default")
      (node (ref "J2") (pin "3") (pinfunction "GPIO6_3") (pintype "bidirectional"))
      (node (ref "U1") (pin "30") (pinfunction "P207/TXD4/SSLA2_A/QSSL_30") (pintype "bidirectional"))
    )
    (net (code "27") (name "Net-(CHG-Pad1)") (class "Default")
      (node (ref "CHG") (pin "1") (pinfunction "1_1") (pintype "passive"))
      (node (ref "D5") (pin "A") (pinfunction "A_A") (pintype "passive"))
    )
    (net (code "28") (name "Net-(CHG-Pad2)") (class "Default")
      (node (ref "CHG") (pin "2") (pinfunction "2_2") (pintype "passive"))
      (node (ref "R9") (pin "1") (pinfunction "1_1") (pintype "passive"))
    )
    (net (code "29") (name "Net-(D1-Pad1)") (class "Default")
      (node (ref "D1") (pin "1") (pinfunction "1_1") (pintype "bidirectional"))
      (node (ref "J1") (pin "A6") (pinfunction "D+_A6") (pintype "bidirectional"))
      (node (ref "J1") (pin "B6") (pinfunction "D+_B6") (pintype "bidirectional"))
    )
    (net (code "30") (name "Net-(D1-Pad3)") (class "Default")
      (node (ref "D1") (pin "3") (pinfunction "3_3") (pintype "bidirectional"))
      (node (ref "J1") (pin "A7") (pinfunction "D-_A7") (pintype "bidirectional"))
      (node (ref "J1") (pin "B7") (pinfunction "D-_B7") (pintype "bidirectional"))
    )
    (net (code "31") (name "Net-(D2-PadC)") (class "Default")
      (node (ref "D2") (pin "C") (pinfunction "C_C") (pintype "passive"))
      (node (ref "R5") (pin "2") (pinfunction "2_2") (pintype "passive"))
    )
    (net (code "32") (name "Net-(D6-PadC)") (class "Default")
      (node (ref "D6") (pin "C") (pinfunction "C_C") (pintype "passive"))
      (node (ref "R12") (pin "2") (pinfunction "2_2") (pintype "passive"))
    )
    (net (code "33") (name "Net-(I2C-Pad1)") (class "Default")
      (node (ref "I2C") (pin "1") (pinfunction "1_1") (pintype "passive"))
      (node (ref "R6") (pin "2") (pinfunction "2_2") (pintype "passive"))
    )
    (net (code "34") (name "Net-(I2C-Pad3)") (class "Default")
      (node (ref "I2C") (pin "3") (pinfunction "3_3") (pintype "passive"))
      (node (ref "R7") (pin "2") (pinfunction "2_2") (pintype "passive"))
    )
    (net (code "35") (name "Net-(J1-CC1)") (class "Default")
      (node (ref "J1") (pin "A5") (pinfunction "CC1_A5") (pintype "bidirectional"))
      (node (ref "R4") (pin "2") (pinfunction "2_2") (pintype "passive"))
    )
    (net (code "36") (name "Net-(J1-CC2)") (class "Default")
      (node (ref "J1") (pin "B5") (pinfunction "CC2_B5") (pintype "bidirectional"))
      (node (ref "R3") (pin "2") (pinfunction "2_2") (pintype "passive"))
    )
    (net (code "37") (name "Net-(J1-SHLD-PadSHLD1)") (class "Default")
      (node (ref "J1") (pin "SHLD1") (pinfunction "SHLD_SHLD1") (pintype "bidirectional"))
      (node (ref "J1") (pin "SHLD2") (pinfunction "SHLD_SHLD2") (pintype "bidirectional"))
      (node (ref "J1") (pin "SHLD3") (pinfunction "SHLD_SHLD3") (pintype "bidirectional"))
      (node (ref "J1") (pin "SHLD4") (pinfunction "SHLD_SHLD4") (pintype "bidirectional"))
      (node (ref "J1") (pin "SHLD5") (pinfunction "SHLD_SHLD5") (pintype "bidirectional"))
      (node (ref "J1") (pin "SHLD6") (pinfunction "SHLD_SHLD6") (pintype "bidirectional"))
      (node (ref "J1") (pin "SHLD7") (pinfunction "SHLD_SHLD7") (pintype "bidirectional"))
      (node (ref "J1") (pin "SHLD8") (pinfunction "SHLD_SHLD8") (pintype "bidirectional"))
      (node (ref "SHLD") (pin "2") (pinfunction "2_2") (pintype "passive"))
    )
    (net (code "38") (name "Net-(JP4-Pad2)") (class "Default")
      (node (ref "JP4") (pin "2") (pinfunction "2_2") (pintype "passive"))
      (node (ref "R12") (pin "1") (pinfunction "1_1") (pintype "passive"))
    )
    (net (code "39") (name "Net-(Q1-G)") (class "Default")
      (node (ref "Q1") (pin "1") (pinfunction "G_1") (pintype "bidirectional"))
      (node (ref "R15") (pin "2") (pinfunction "2_2") (pintype "passive"))
    )
    (net (code "40") (name "Net-(Q2-G)") (class "Default")
      (node (ref "Q2") (pin "1") (pinfunction "G_1") (pintype "bidirectional"))
      (node (ref "R13") (pin "2") (pinfunction "2_2") (pintype "passive"))
    )
    (net (code "41") (name "Net-(RN1A-2)") (class "Default")
      (node (ref "RN1") (pin "16") (pinfunction "2_16") (pintype "passive"))
      (node (ref "U1") (pin "59") (pinfunction "P608/GTIOC4B_59") (pintype "bidirectional"))
    )
    (net (code "42") (name "Net-(RN1B-2)") (class "Default")
      (node (ref "RN1") (pin "15") (pinfunction "2_15") (pintype "passive"))
      (node (ref "U1") (pin "60") (pinfunction "P609/CTX1/GTIOC5A/AGTO5_60") (pintype "bidirectional"))
    )
    (net (code "43") (name "Net-(RN1C-2)") (class "Default")
      (node (ref "RN1") (pin "14") (pinfunction "2_14") (pintype "passive"))
      (node (ref "U1") (pin "61") (pinfunction "P610/CRX1/CTS7/GTIOC5B/AGTO4_61") (pintype "bidirectional"))
    )
    (net (code "44") (name "Net-(RN1D-2)") (class "Default")
      (node (ref "RN1") (pin "13") (pinfunction "2_13") (pintype "passive"))
      (node (ref "U1") (pin "67") (pinfunction "P600/SCK9/GTIOC6B_67") (pintype "bidirectional"))
    )
    (net (code "45") (name "Net-(RN1E-2)") (class "Default")
      (node (ref "RN1") (pin "12") (pinfunction "2_12") (pintype "passive"))
      (node (ref "U1") (pin "68") (pinfunction "P107/CTS8_RTS8_68") (pintype "bidirectional"))
    )
    (net (code "46") (name "Net-(RN1H-2)") (class "Default")
      (node (ref "RN1") (pin "9") (pinfunction "2_9") (pintype "passive"))
      (node (ref "U1") (pin "92") (pinfunction "P008/AN008_92") (pintype "bidirectional"))
    )
    (net (code "47") (name "Net-(RN3C-2)") (class "Default")
      (node (ref "RN3") (pin "14") (pinfunction "2_14") (pintype "passive"))
      (node (ref "U1") (pin "18") (pinfunction "P414/SDA2/CTS0/SSLB1_B/SD0WP_18") (pintype "bidirectional"))
    )
    (net (code "48") (name "Net-(RN3D-2)") (class "Default")
      (node (ref "RN3") (pin "13") (pinfunction "2_13") (pintype "passive"))
      (node (ref "U1") (pin "19") (pinfunction "P413/CTS0_RTS0/SSLB0_B/SD0CLK_A_19") (pintype "bidirectional"))
    )
    (net (code "49") (name "Net-(RN3E-2)") (class "Default")
      (node (ref "RN3") (pin "12") (pinfunction "2_12") (pintype "passive"))
      (node (ref "U1") (pin "20") (pinfunction "P412/SCK0/CTS3/RSPCKB_B_20") (pintype "bidirectional"))
    )
    (net (code "50") (name "Net-(RN3F-2)") (class "Default")
      (node (ref "RN3") (pin "11") (pinfunction "2_11") (pintype "passive"))
      (node (ref "U1") (pin "21") (pinfunction "P411/TXD0/CTS3_RTS3/PICOB_B_21") (pintype "bidirectional"))
    )
    (net (code "51") (name "Net-(RN3G-1)") (class "Default")
      (node (ref "C1") (pin "2") (pinfunction "2_2") (pintype "passive"))
      (node (ref "R1") (pin "1") (pinfunction "1_1") (pintype "passive"))
      (node (ref "RN3") (pin "7") (pinfunction "1_7") (pintype "passive"))
    )
    (net (code "52") (name "Net-(RN3G-2)") (class "Default")
      (node (ref "R2") (pin "2") (pinfunction "2_2") (pintype "passive"))
      (node (ref "RN3") (pin "10") (pinfunction "2_10") (pintype "passive"))
      (node (ref "U1") (pin "25") (pinfunction "P407/USB_VBUS/CTS4_RTS4_25") (pintype "bidirectional"))
    )
    (net (code "53") (name "Net-(RN3H-2)") (class "Default")
      (node (ref "RN3") (pin "9") (pinfunction "2_9") (pintype "passive"))
      (node (ref "U1") (pin "36") (pinfunction "P209/QIO2/SD0WP/GTOVUP_36") (pintype "bidirectional"))
    )
    (net (code "54") (name "Net-(RN4B-2)") (class "Default")
      (node (ref "RN4") (pin "15") (pinfunction "2_15") (pintype "passive"))
      (node (ref "U1") (pin "43") (pinfunction "P305/TXD6/QSPCLK/GTOWUP_43") (pintype "bidirectional"))
    )
    (net (code "55") (name "Net-(RN4C-2)") (class "Default")
      (node (ref "RN4") (pin "14") (pinfunction "2_14") (pintype "passive"))
      (node (ref "U1") (pin "42") (pinfunction "P306/SCK6/QSSL/GTOULO_D_42") (pintype "bidirectional"))
    )
    (net (code "56") (name "Net-(RN4D-2)") (class "Default")
      (node (ref "RN4") (pin "13") (pinfunction "2_13") (pintype "passive"))
      (node (ref "U1") (pin "41") (pinfunction "P307/CTS6_RTS6/QIO0/GTOUUP_D_41") (pintype "bidirectional"))
    )
    (net (code "57") (name "Net-(RN4E-2)") (class "Default")
      (node (ref "RN4") (pin "12") (pinfunction "2_12") (pintype "passive"))
      (node (ref "U1") (pin "48") (pinfunction "P302/TXD2/SSLA3_B/GTOUUP_48") (pintype "bidirectional"))
    )
    (net (code "58") (name "Net-(RN4F-2)") (class "Default")
      (node (ref "RN4") (pin "11") (pinfunction "2_11") (pintype "passive"))
      (node (ref "U1") (pin "56") (pinfunction "P113/RXD2/SSILRCK0_B/GTIOC2A_56") (pintype "bidirectional"))
    )
    (net (code "59") (name "Net-(RN4G-2)") (class "Default")
      (node (ref "RN4") (pin "10") (pinfunction "2_10") (pintype "passive"))
      (node (ref "U1") (pin "57") (pinfunction "P114/CTS9/SSIRXD0_B/GTIOC2B_57") (pintype "bidirectional"))
    )
    (net (code "60") (name "Net-(RN5C-1)") (class "Default")
      (node (ref "RN5") (pin "3") (pinfunction "1_3") (pintype "passive"))
      (node (ref "U1") (pin "98") (pinfunction "P002/AN002/AN102_98") (pintype "bidirectional"))
    )
    (net (code "61") (name "Net-(RN5D-1)") (class "Default")
      (node (ref "RN5") (pin "4") (pinfunction "1_4") (pintype "passive"))
      (node (ref "U1") (pin "97") (pinfunction "P003/AN003_97") (pintype "bidirectional"))
    )
    (net (code "62") (name "Net-(RN5E-1)") (class "Default")
      (node (ref "RN5") (pin "5") (pinfunction "1_5") (pintype "passive"))
      (node (ref "U1") (pin "96") (pinfunction "P004/AN004_96") (pintype "bidirectional"))
    )
    (net (code "63") (name "Net-(RN5F-1)") (class "Default")
      (node (ref "RN5") (pin "6") (pinfunction "1_6") (pintype "passive"))
      (node (ref "U1") (pin "95") (pinfunction "P005/AN005_95") (pintype "bidirectional"))
    )
    (net (code "64") (name "Net-(RN5G-1)") (class "Default")
      (node (ref "RN5") (pin "7") (pinfunction "1_7") (pintype "passive"))
      (node (ref "U1") (pin "94") (pinfunction "P006/AN006_94") (pintype "bidirectional"))
    )
    (net (code "65") (name "Net-(RN5H-1)") (class "Default")
      (node (ref "RN5") (pin "8") (pinfunction "1_8") (pintype "passive"))
      (node (ref "U1") (pin "93") (pinfunction "P007/AN007_93") (pintype "bidirectional"))
    )
    (net (code "66") (name "Net-(U1B-VREFH)") (class "Default")
      (node (ref "C26") (pin "1") (pinfunction "1_1") (pintype "passive"))
      (node (ref "C27") (pin "1") (pinfunction "1_1") (pintype "passive"))
      (node (ref "FB2") (pin "1") (pinfunction "1_1") (pintype "passive"))
      (node (ref "U1") (pin "87") (pinfunction "VREFH_87") (pintype "bidirectional"))
      (node (ref "U1") (pin "91") (pinfunction "VREFH0_91") (pintype "bidirectional"))
    )
    (net (code "67") (name "Net-(U1C-VBATT)") (class "Default")
      (node (ref "BAT") (pin "2") (pinfunction "2_2") (pintype "passive"))
      (node (ref "U1") (pin "8") (pinfunction "VBATT_8") (pintype "bidirectional"))
    )
    (net (code "68") (name "Net-(U1C-VCL)") (class "Default")
      (node (ref "C12") (pin "1") (pinfunction "1_1") (pintype "passive"))
      (node (ref "U1") (pin "64") (pinfunction "VCL_64") (pintype "bidirectional"))
    )
    (net (code "69") (name "Net-(U1C-VCL0)") (class "Default")
      (node (ref "C11") (pin "1") (pinfunction "1_1") (pintype "passive"))
      (node (ref "U1") (pin "9") (pinfunction "VCL0_9") (pintype "bidirectional"))
    )
    (net (code "70") (name "Net-(U1H-P212{slash}EXTAL{slash}RXD1)") (class "Default")
      (node (ref "U1") (pin "14") (pinfunction "P212/EXTAL/RXD1_14") (pintype "bidirectional"))
      (node (ref "Y1") (pin "1") (pinfunction "1_1") (pintype "passive"))
    )
    (net (code "71") (name "Net-(U1H-P213{slash}XTAL{slash}TXD1)") (class "Default")
      (node (ref "U1") (pin "13") (pinfunction "P213/XTAL/TXD1_13") (pintype "bidirectional"))
      (node (ref "Y1") (pin "3") (pinfunction "2_3") (pintype "passive"))
    )
    (net (code "72") (name "Net-(U1H-XCIN)") (class "Default")
      (node (ref "C10") (pin "2") (pinfunction "2_2") (pintype "passive"))
      (node (ref "U1") (pin "10") (pinfunction "XCIN_10") (pintype "bidirectional"))
      (node (ref "Y2") (pin "P$1") (pinfunction "1_P$1") (pintype "passive"))
    )
    (net (code "73") (name "Net-(U1H-XCOUT)") (class "Default")
      (node (ref "C9") (pin "2") (pinfunction "2_2") (pintype "passive"))
      (node (ref "U1") (pin "11") (pinfunction "XCOUT_11") (pintype "bidirectional"))
      (node (ref "Y2") (pin "P$2") (pinfunction "2_P$2") (pintype "passive"))
    )
    (net (code "74") (name "Net-(U3-PROG)") (class "Default")
      (node (ref "R11") (pin "2") (pinfunction "2_2") (pintype "passive"))
      (node (ref "U3") (pin "5") (pinfunction "PROG_5") (pintype "input"))
    )
    (net (code "75") (name "Net-(U3-STAT)") (class "Default")
      (node (ref "D5") (pin "C") (pinfunction "C_C") (pintype "passive"))
      (node (ref "U3") (pin "1") (pinfunction "STAT_1") (pintype "output"))
    )
    (net (code "76") (name "QIO0") (class "Default")
      (node (ref "U1") (pin "73") (pinfunction "P102/QIO0/SCK0/RSPCKB_A_73") (pintype "bidirectional"))
      (node (ref "U5") (pin "5") (pinfunction "D0/DI_5") (pintype "bidirectional"))
    )
    (net (code "77") (name "QIO1") (class "Default")
      (node (ref "U1") (pin "74") (pinfunction "P101/QIO1/TXD0/CTS1_RTS1/PICOB_A_74") (pintype "bidirectional"))
      (node (ref "U5") (pin "2") (pinfunction "D1/DO_2") (pintype "bidirectional"))
    )
    (net (code "78") (name "QIO2") (class "Default")
      (node (ref "U1") (pin "71") (pinfunction "P104/QIO2/RXD8/SSLB1_A_71") (pintype "bidirectional"))
      (node (ref "U5") (pin "3") (pinfunction "D2/~{WP}_3") (pintype "bidirectional"))
    )
    (net (code "79") (name "QIO3") (class "Default")
      (node (ref "U1") (pin "72") (pinfunction "P103/QIO3/SSLB0_A/CTS0_RTS0_72") (pintype "bidirectional"))
      (node (ref "U5") (pin "7") (pinfunction "D3/~{RESET}_7") (pintype "bidirectional"))
    )
    (net (code "80") (name "QSPCLK") (class "Default")
      (node (ref "U1") (pin "75") (pinfunction "P100/QSPCLK/RXD0/SCK1/POCIB_A_75") (pintype "bidirectional"))
      (node (ref "U5") (pin "6") (pinfunction "CLK_6") (pintype "bidirectional"))
    )
    (net (code "81") (name "RA6_SWCLK{slash}TCK") (class "Default")
      (node (ref "J4") (pin "3") (pinfunction "3_3") (pintype "bidirectional"))
      (node (ref "U1") (pin "50") (pinfunction "P300/TCK/SWCLK/SSLA1_B_50") (pintype "bidirectional"))
    )
    (net (code "82") (name "RA6_SWDIO{slash}TMS") (class "Default")
      (node (ref "J4") (pin "2") (pinfunction "2_2") (pintype "bidirectional"))
      (node (ref "U1") (pin "51") (pinfunction "P108/TMS/SWDIO/CTS9_RTS9_51") (pintype "bidirectional"))
    )
    (net (code "83") (name "RA6_SWO{slash}TDO{slash}PICO{slash}D18") (class "Default")
      (node (ref "J2") (pin "17") (pinfunction "PICO_17") (pintype "bidirectional"))
      (node (ref "J4") (pin "4") (pinfunction "4_4") (pintype "bidirectional"))
      (node (ref "U1") (pin "52") (pinfunction "P109/TDO/SWO/PICOA_B/TXD9_52") (pintype "bidirectional"))
    )
    (net (code "84") (name "RA6_TDI{slash}POCI{slash}D17") (class "Default")
      (node (ref "J2") (pin "16") (pinfunction "POCI_16") (pintype "bidirectional"))
      (node (ref "U1") (pin "53") (pinfunction "P110/TDI/POCIA_B/CTS2_RTS2/RXD9_53") (pintype "bidirectional"))
    )
    (net (code "85") (name "RGB_DIN") (class "Default")
      (node (ref "D4") (pin "DI") (pinfunction "DI_DI") (pintype "bidirectional"))
      (node (ref "U1") (pin "70") (pinfunction "P105/TXD8/SSLB2_A_70") (pintype "bidirectional"))
    )
    (net (code "86") (name "RGB_DOUT") (class "Default")
      (node (ref "D4") (pin "DO") (pinfunction "DO_DO") (pintype "bidirectional"))
      (node (ref "TP1") (pin "1") (pinfunction "1_1") (pintype "bidirectional"))
    )
    (net (code "87") (name "RX_RA6{slash}TX_DA14531") (class "Default")
      (node (ref "TP6") (pin "1") (pinfunction "1_1") (pintype "bidirectional"))
      (node (ref "U1") (pin "66") (pinfunction "P601/RXD9/GTIOC6A_66") (pintype "bidirectional"))
      (node (ref "U2") (pin "5") (pinfunction "P0_6/UTX_5") (pintype "bidirectional"))
    )
    (net (code "88") (name "SCK{slash}D19") (class "Default")
      (node (ref "J2") (pin "18") (pinfunction "SCK_18") (pintype "bidirectional"))
      (node (ref "U1") (pin "54") (pinfunction "P111/RSPCKA_B/SCK2/SCK9_54") (pintype "bidirectional"))
    )
    (net (code "89") (name "SCL{slash}D16") (class "Default")
      (node (ref "J2") (pin "2") (pinfunction "SCL_2") (pintype "bidirectional"))
      (node (ref "J3") (pin "4") (pinfunction "4_4") (pintype "passive"))
      (node (ref "R7") (pin "1") (pinfunction "1_1") (pintype "passive"))
      (node (ref "U1") (pin "1") (pinfunction "P400/SCL0_A/SCK4/SCK7/AUDIO_CLK_1") (pintype "bidirectional"))
      (node (ref "U7") (pin "7") (pinfunction "SCL_7") (pintype "output"))
    )
    (net (code "90") (name "SDA{slash}D15") (class "Default")
      (node (ref "J2") (pin "1") (pinfunction "SDA_1") (pintype "bidirectional"))
      (node (ref "J3") (pin "3") (pinfunction "3_3") (pintype "passive"))
      (node (ref "R6") (pin "1") (pinfunction "1_1") (pintype "passive"))
      (node (ref "U1") (pin "2") (pinfunction "P401/SDA0_A/TXD7/CTS4_RTS4_2") (pintype "bidirectional"))
      (node (ref "U7") (pin "8") (pinfunction "SDA_8") (pintype "input"))
    )
    (net (code "91") (name "SDCLK") (class "Default")
      (node (ref "J7") (pin "5") (pinfunction "CLK/SCK_5") (pintype "bidirectional"))
      (node (ref "U1") (pin "33") (pinfunction "P214/SD0CLK_B/QSPCLK_33") (pintype "bidirectional"))
    )
    (net (code "92") (name "SDCMD") (class "Default")
      (node (ref "J7") (pin "3") (pinfunction "CMD/SDI_3") (pintype "bidirectional"))
      (node (ref "U1") (pin "34") (pinfunction "P211/SD0CMD_B/QIO0_34") (pintype "bidirectional"))
    )
    (net (code "93") (name "SDDAT0") (class "Default")
      (node (ref "J7") (pin "7") (pinfunction "DAT0/SDO_7") (pintype "bidirectional"))
      (node (ref "U1") (pin "37") (pinfunction "P208/SD0DAT0_B/QIO3_37") (pintype "bidirectional"))
    )
    (net (code "94") (name "SDDAT1") (class "Default")
      (node (ref "J7") (pin "8") (pinfunction "DAT1_8") (pintype "bidirectional"))
      (node (ref "U1") (pin "22") (pinfunction "P410/SD0DAT1_A/RXD0/SCL2/SCK3_22") (pintype "bidirectional"))
    )
    (net (code "95") (name "SDDAT2") (class "Default")
      (node (ref "J7") (pin "1") (pinfunction "DAT2_1") (pintype "bidirectional"))
      (node (ref "U1") (pin "31") (pinfunction "P206/SD0DAT2_A/USB_VBUSEN/RXD4_31") (pintype "bidirectional"))
    )
    (net (code "96") (name "SDDAT3") (class "Default")
      (node (ref "J7") (pin "2") (pinfunction "DAT3/~{CS}_2") (pintype "bidirectional"))
      (node (ref "U1") (pin "32") (pinfunction "P205/SD0DAT3_A/TXD4/CTS9_RTS9_32") (pintype "bidirectional"))
    )
    (net (code "97") (name "SDDET") (class "Default")
      (node (ref "J7") (pin "9") (pinfunction "DET_9") (pintype "bidirectional"))
      (node (ref "U1") (pin "35") (pinfunction "P210/SD0CD/QIO1_35") (pintype "bidirectional"))
    )
    (net (code "98") (name "STAT_LED") (class "Default")
      (node (ref "D2") (pin "A") (pinfunction "A_A") (pintype "passive"))
      (node (ref "U1") (pin "69") (pinfunction "P106/SCK8/SSLB3_A_69") (pintype "bidirectional"))
    )
    (net (code "99") (name "TX_RA6{slash}RX_DA14531") (class "Default")
      (node (ref "TP5") (pin "1") (pinfunction "1_1") (pintype "bidirectional"))
      (node (ref "U1") (pin "65") (pinfunction "P602/TXD9/GTIOC7B_65") (pintype "bidirectional"))
      (node (ref "U2") (pin "14") (pinfunction "P0_5/URX_14") (pintype "bidirectional"))
    )
    (net (code "100") (name "UART_RX{slash}D21") (class "Default")
      (node (ref "J2") (pin "15") (pinfunction "RX_15") (pintype "bidirectional"))
      (node (ref "U1") (pin "24") (pinfunction "P408/RXD3/SCL0_B/USB_ID_24") (pintype "bidirectional"))
    )
    (net (code "101") (name "UART_TX{slash}D20") (class "Default")
      (node (ref "J2") (pin "14") (pinfunction "TX_14") (pintype "bidirectional"))
      (node (ref "U1") (pin "23") (pinfunction "P409/TXD3/SDA2/USB_EXICEN_23") (pintype "bidirectional"))
    )
    (net (code "102") (name "USBD_N") (class "Default")
      (node (ref "D1") (pin "4") (pinfunction "4_4") (pintype "bidirectional"))
      (node (ref "U1") (pin "27") (pinfunction "USB_DM_27") (pintype "bidirectional"))
    )
    (net (code "103") (name "USBD_P") (class "Default")
      (node (ref "D1") (pin "6") (pinfunction "6_6") (pintype "bidirectional"))
      (node (ref "U1") (pin "28") (pinfunction "USB_DP_28") (pintype "bidirectional"))
    )
    (net (code "104") (name "VIN") (class "Default")
      (node (ref "C14") (pin "1") (pinfunction "1_1") (pintype "passive"))
      (node (ref "C17") (pin "1") (pinfunction "1_1") (pintype "passive"))
      (node (ref "C20") (pin "1") (pinfunction "1_1") (pintype "passive"))
      (node (ref "R10") (pin "2") (pinfunction "2_2") (pintype "passive"))
      (node (ref "U4") (pin "1") (pinfunction "IN_1") (pintype "input"))
      (node (ref "U6") (pin "1") (pinfunction "IN_1") (pintype "input"))
      (node (ref "U8") (pin "2") (pinfunction "VOUT_2") (pintype "bidirectional"))
      (node (ref "U8") (pin "7") (pinfunction "VOUT_7") (pintype "bidirectional"))
    )
    (net (code "105") (name "VREF1") (class "Default")
      (node (ref "C19") (pin "1") (pinfunction "1_1") (pintype "passive"))
      (node (ref "FB2") (pin "2") (pinfunction "2_2") (pintype "passive"))
      (node (ref "J2") (pin "26") (pinfunction "AREF/NC_26") (pintype "bidirectional"))
      (node (ref "U6") (pin "5") (pinfunction "OUT_5") (pintype "passive"))
    )
    (net (code "106") (name "VREFEN") (class "Default")
      (node (ref "RN1") (pin "6") (pinfunction "1_6") (pintype "passive"))
      (node (ref "TP2") (pin "1") (pinfunction "1_1") (pintype "bidirectional"))
      (node (ref "U1") (pin "76") (pinfunction "P500/USB_VBUSEN/CTS5/QSPCLK_76") (pintype "bidirectional"))
      (node (ref "U6") (pin "3") (pinfunction "EN_3") (pintype "input"))
    )
    (net (code "107") (name "VREG_EN") (class "Default")
      (node (ref "J2") (pin "11") (pinfunction "EN_11") (pintype "bidirectional"))
      (node (ref "R10") (pin "1") (pinfunction "1_1") (pintype "passive"))
      (node (ref "U4") (pin "3") (pinfunction "EN_3") (pintype "input"))
    )
    (net (code "108") (name "V_BATT") (class "Default")
      (node (ref "C15") (pin "1") (pinfunction "1_1") (pintype "passive"))
      (node (ref "C18") (pin "2") (pinfunction "2_2") (pintype "passive"))
      (node (ref "J2") (pin "12") (pinfunction "V_BATT_12") (pintype "bidirectional"))
      (node (ref "J6") (pin "2") (pinfunction "+_2") (pintype "bidirectional"))
      (node (ref "U3") (pin "3") (pinfunction "VBAT_3") (pintype "power_in"))
      (node (ref "U7") (pin "2") (pinfunction "CELL_2") (pintype "input"))
      (node (ref "U7") (pin "3") (pinfunction "VDD_3") (pintype "bidirectional"))
      (node (ref "U8") (pin "3") (pinfunction "VIN1_3") (pintype "bidirectional"))
    )
    (net (code "109") (name "V_USB") (class "Default")
      (node (ref "C13") (pin "1") (pinfunction "1_1") (pintype "passive"))
      (node (ref "D1") (pin "5") (pinfunction "5_5") (pintype "power_in"))
      (node (ref "J1") (pin "VBUS1") (pinfunction "VBUS_VBUS1") (pintype "bidirectional"))
      (node (ref "J1") (pin "VBUS2") (pinfunction "VBUS_VBUS2") (pintype "bidirectional"))
      (node (ref "J2") (pin "10") (pinfunction "V_USB_10") (pintype "bidirectional"))
      (node (ref "R1") (pin "2") (pinfunction "2_2") (pintype "passive"))
      (node (ref "R9") (pin "2") (pinfunction "2_2") (pintype "passive"))
      (node (ref "U3") (pin "4") (pinfunction "VIN_4") (pintype "power_in"))
      (node (ref "U8") (pin "6") (pinfunction "VIN2_6") (pintype "bidirectional"))
    )
    (net (code "110") (name "unconnected-(J6-PAD1-PadNC1)") (class "Default")
      (node (ref "J6") (pin "NC1") (pinfunction "PAD1_NC1") (pintype "bidirectional"))
    )
    (net (code "111") (name "unconnected-(J6-PAD2-PadNC2)") (class "Default")
      (node (ref "J6") (pin "NC2") (pinfunction "PAD2_NC2") (pintype "bidirectional"))
    )
    (net (code "112") (name "~{CTS_RA6{slash}RTS_DA14531}") (class "Default")
      (node (ref "TP7") (pin "1") (pinfunction "1_1") (pintype "bidirectional"))
      (node (ref "U1") (pin "47") (pinfunction "P303/CTS9/GTIOC7B_47") (pintype "bidirectional"))
      (node (ref "U2") (pin "13") (pinfunction "P0_7/URTS_13") (pintype "bidirectional"))
    )
    (net (code "113") (name "~{DA14531_RST}") (class "Default")
      (node (ref "J5") (pin "6") (pinfunction "6_6") (pintype "bidirectional"))
      (node (ref "R13") (pin "1") (pinfunction "1_1") (pintype "passive"))
      (node (ref "R16") (pin "2") (pinfunction "2_2") (pintype "passive"))
      (node (ref "U1") (pin "58") (pinfunction "P115/SSITXD0_B/GTIOC4A_58") (pintype "bidirectional"))
    )
    (net (code "114") (name "~{FG_ALRT}") (class "Default")
      (node (ref "RN5") (pin "1") (pinfunction "1_1") (pintype "passive"))
      (node (ref "U1") (pin "100") (pinfunction "P000/AN000/AN100_100") (pintype "bidirectional"))
      (node (ref "U7") (pin "5") (pinfunction "~{ALRT}_5") (pintype "bidirectional"))
    )
    (net (code "115") (name "~{NMI}") (class "Default")
      (node (ref "RN4") (pin "16") (pinfunction "2_16") (pintype "passive"))
      (node (ref "TP9") (pin "1") (pinfunction "1_1") (pintype "bidirectional"))
      (node (ref "U1") (pin "40") (pinfunction "P200/NMI_40") (pintype "bidirectional"))
    )
    (net (code "116") (name "~{QCS}") (class "Default")
      (node (ref "RN1") (pin "7") (pinfunction "1_7") (pintype "passive"))
      (node (ref "U1") (pin "77") (pinfunction "P501/QSSL/TXD5/USB_OVRCURA_77") (pintype "bidirectional"))
      (node (ref "U5") (pin "1") (pinfunction "~{CS}_1") (pintype "bidirectional"))
    )
    (net (code "117") (name "~{RA6M5_RESET}") (class "Default")
      (node (ref "J2") (pin "28") (pinfunction "~{RESET}_28") (pintype "bidirectional"))
      (node (ref "J4") (pin "6") (pinfunction "6_6") (pintype "bidirectional"))
      (node (ref "R14") (pin "1") (pinfunction "1_1") (pintype "passive"))
      (node (ref "S2") (pin "3") (pinfunction "2_3") (pintype "passive"))
      (node (ref "S2") (pin "4") (pinfunction "2_4") (pintype "passive"))
      (node (ref "U1") (pin "38") (pinfunction "~{RES}_38") (pintype "bidirectional"))
      (node (ref "U2") (pin "8") (pinfunction "P0_11_8") (pintype "bidirectional"))
    )
    (net (code "118") (name "~{RTS_RA6{slash}CTS_DA14531}") (class "Default")
      (node (ref "TP8") (pin "1") (pinfunction "1_1") (pintype "bidirectional"))
      (node (ref "U1") (pin "49") (pinfunction "P301/CTS9_RTS9/RXD2/SSLA2_B_49") (pintype "bidirectional"))
      (node (ref "U2") (pin "16") (pinfunction "P0_8/UCTS_16") (pintype "bidirectional"))
    )
    (net (code "119") (name "~{SD_EN}") (class "Default")
      (node (ref "R15") (pin "1") (pinfunction "1_1") (pintype "passive"))
      (node (ref "RN3") (pin "16") (pinfunction "2_16") (pintype "passive"))
      (node (ref "U1") (pin "16") (pinfunction "P708/AUDIO_CLK/RXD1/CECIO_16") (pintype "bidirectional"))
    )
    (net (code "120") (name "~{USR_BTN}") (class "Default")
      (node (ref "RN3") (pin "15") (pinfunction "2_15") (pintype "passive"))
      (node (ref "S1") (pin "1") (pinfunction "1_1") (pintype "passive"))
      (node (ref "S1") (pin "2") (pinfunction "1_2") (pintype "passive"))
      (node (ref "U1") (pin "17") (pinfunction "P415/USB_VBUSEN/SCL2/SSLB2_B_17") (pintype "bidirectional"))
    )
  )
)
